# Sheet2.net
KiCad netlist of a schematic drawn in Altium Designer
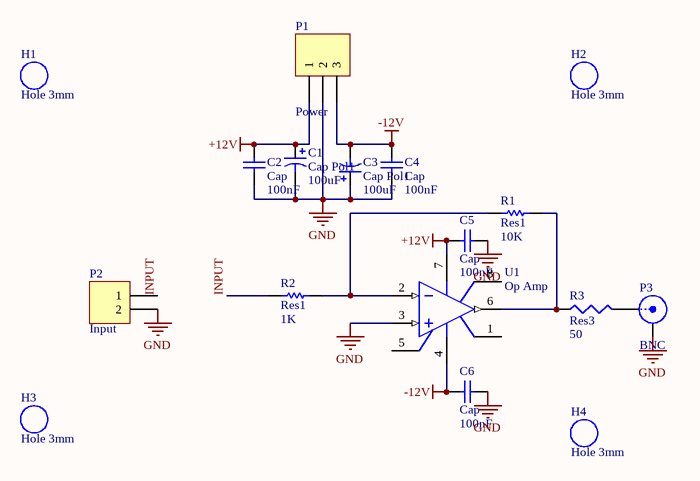
[diagram p0: Sheet2.SchDoc]

(export (version "E")
  (design (tool "Eeschema 10.0.6"))
  (components
    (comp (ref "C1")
      (value "Cap Pol1")
      (footprint "RB7.6-15")
      (description "Polarized Capacitor (Radial)")
      (fields (field (name "ALTIUM_VALUE") "100uF") (field (name "PUBLISHER") "Altium Limited"))
      (libsource (lib "Miscellaneous Devices") (part "Cap Pol1"))
    )
    (comp (ref "C2")
      (value "Cap")
      (footprint "RAD-0.3")
      (description "Capacitor")
      (fields (field (name "ALTIUM_VALUE") "100nF") (field (name "PUBLISHER") "Altium Limited"))
      (libsource (lib "Miscellaneous Devices") (part "Cap"))
    )
    (comp (ref "C3")
      (value "Cap Pol1")
      (footprint "RB7.6-15")
      (description "Polarized Capacitor (Radial)")
      (fields (field (name "ALTIUM_VALUE") "100uF") (field (name "PUBLISHER") "Altium Limited"))
      (libsource (lib "Miscellaneous Devices") (part "Cap Pol1"))
    )
    (comp (ref "C4")
      (value "Cap")
      (footprint "RAD-0.3")
      (description "Capacitor")
      (fields (field (name "ALTIUM_VALUE") "100nF") (field (name "PUBLISHER") "Altium Limited"))
      (libsource (lib "Miscellaneous Devices") (part "Cap"))
    )
    (comp (ref "C5")
      (value "Cap")
      (footprint "RAD-0.3")
      (description "Capacitor")
      (fields (field (name "ALTIUM_VALUE") "100nF") (field (name "PUBLISHER") "Altium Limited"))
      (libsource (lib "Miscellaneous Devices") (part "Cap"))
    )
    (comp (ref "C6")
      (value "Cap")
      (footprint "RAD-0.3")
      (description "Capacitor")
      (fields (field (name "ALTIUM_VALUE") "100nF") (field (name "PUBLISHER") "Altium Limited"))
      (libsource (lib "Miscellaneous Devices") (part "Cap"))
    )
    (comp (ref "H1")
      (value "Hole 3mm")
      (footprint "Hole 3mm")
      (libsource (lib "ECE LIB new") (part "Hole 3mm"))
    )
    (comp (ref "H2")
      (value "Hole 3mm")
      (footprint "Hole 3mm")
      (libsource (lib "ECE LIB new") (part "Hole 3mm"))
    )
    (comp (ref "H3")
      (value "Hole 3mm")
      (footprint "Hole 3mm")
      (libsource (lib "ECE LIB new") (part "Hole 3mm"))
    )
    (comp (ref "H4")
      (value "Hole 3mm")
      (footprint "Hole 3mm")
      (libsource (lib "ECE LIB new") (part "Hole 3mm"))
    )
    (comp (ref "P1")
      (value "Power")
      (footprint "HDR1X3H")
      (description "Header, 3-Pin, Right Angle")
      (fields (field (name "PUBLISHER") "Altium Limited"))
      (libsource (lib "Miscellaneous Connectors") (part "Header 3H"))
    )
    (comp (ref "P2")
      (value "Input")
      (footprint "HDR1X2")
      (description "Header, 2-Pin")
      (fields (field (name "PUBLISHER") "Altium Limited"))
      (libsource (lib "Miscellaneous Connectors") (part "Header 2"))
    )
    (comp (ref "P3")
      (value "BNC")
      (footprint "BNC_RA CON")
      (description "BNC Elbow Connector")
      (fields (field (name "PUBLISHER") "Altium Limited"))
      (libsource (lib "Miscellaneous Connectors") (part "BNC"))
    )
    (comp (ref "R1")
      (value "Res1")
      (footprint "AXIAL-0.3")
      (description "Resistor")
      (fields (field (name "ALTIUM_VALUE") "10K") (field (name "PUBLISHER") "Altium Limited"))
      (libsource (lib "Miscellaneous Devices") (part "Res1"))
    )
    (comp (ref "R2")
      (value "Res1")
      (footprint "AXIAL-0.3")
      (description "Resistor")
      (fields (field (name "ALTIUM_VALUE") "1K") (field (name "PUBLISHER") "Altium Limited"))
      (libsource (lib "Miscellaneous Devices") (part "Res1"))
    )
    (comp (ref "R3")
      (value "Res3")
      (footprint "J1-0603")
      (description "Resistor")
      (fields (field (name "ALTIUM_VALUE") "50") (field (name "PUBLISHER") "Altium Limited"))
      (libsource (lib "Miscellaneous Devices") (part "Res3"))
    )
    (comp (ref "U1")
      (value "Op Amp")
      (footprint "DIP-8")
      (description "FET Operational Amplifier")
      (fields (field (name "PUBLISHER") "Altium Limited"))
      (libsource (lib "Miscellaneous Devices") (part "Op Amp"))
    )
  )
  (nets
    (net (code "1") (name "+12V") (class "Default")
      (node (ref "C1") (pin "1") (pinfunction "1_1") (pintype "passive"))
      (node (ref "C2") (pin "2") (pinfunction "2_2") (pintype "passive"))
      (node (ref "C5") (pin "2") (pinfunction "2_2") (pintype "passive"))
      (node (ref "P1") (pin "1") (pinfunction "1_1") (pintype "passive"))
      (node (ref "U1") (pin "7") (pinfunction "V+_7") (pintype "power_in"))
    )
    (net (code "2") (name "-12V") (class "Default")
      (node (ref "C3") (pin "2") (pinfunction "2_2") (pintype "passive"))
      (node (ref "C4") (pin "2") (pinfunction "2_2") (pintype "passive"))
      (node (ref "C6") (pin "2") (pinfunction "2_2") (pintype "passive"))
      (node (ref "P1") (pin "3") (pinfunction "3_3") (pintype "passive"))
      (node (ref "U1") (pin "4") (pinfunction "V-_4") (pintype "power_in"))
    )
    (net (code "3") (name "/INPUT") (class "Default")
      (node (ref "P2") (pin "1") (pinfunction "1_1") (pintype "passive"))
      (node (ref "R2") (pin "1") (pinfunction "1_1") (pintype "passive"))
    )
    (net (code "4") (name "GND") (class "Default")
      (node (ref "C1") (pin "2") (pinfunction "2_2") (pintype "passive"))
      (node (ref "C2") (pin "1") (pinfunction "1_1") (pintype "passive"))
      (node (ref "C3") (pin "1") (pinfunction "1_1") (pintype "passive"))
      (node (ref "C4") (pin "1") (pinfunction "1_1") (pintype "passive"))
      (node (ref "C5") (pin "1") (pinfunction "1_1") (pintype "passive"))
      (node (ref "C6") (pin "1") (pinfunction "1_1") (pintype "passive"))
      (node (ref "P1") (pin "2") (pinfunction "2_2") (pintype "passive"))
      (node (ref "P2") (pin "2") (pinfunction "2_2") (pintype "passive"))
      (node (ref "P3") (pin "2") (pinfunction "Y_2") (pintype "passive"))
      (node (ref "U1") (pin "3") (pinfunction "IN+_3") (pintype "input"))
    )
    (net (code "5") (name "Net-(P3-X)") (class "Default")
      (node (ref "P3") (pin "1") (pinfunction "X_1") (pintype "passive"))
      (node (ref "R3") (pin "2") (pinfunction "2_2") (pintype "passive"))
    )
    (net (code "6") (name "Net-(U1-IN-)") (class "Default")
      (node (ref "R1") (pin "1") (pinfunction "1_1") (pintype "passive"))
      (node (ref "R2") (pin "2") (pinfunction "2_2") (pintype "passive"))
      (node (ref "U1") (pin "2") (pinfunction "IN-_2") (pintype "input"))
    )
    (net (code "7") (name "Net-(U1-OUT)") (class "Default")
      (node (ref "R1") (pin "2") (pinfunction "2_2") (pintype "passive"))
      (node (ref "R3") (pin "1") (pinfunction "1_1") (pintype "passive"))
      (node (ref "U1") (pin "6") (pinfunction "OUT_6") (pintype "output"))
    )
    (net (code "8") (name "unconnected-(U1-OS_NUL-Pad1)") (class "Default")
      (node (ref "U1") (pin "1") (pinfunction "OS_NUL_1") (pintype "passive"))
    )
    (net (code "9") (name "unconnected-(U1-OS_NUL-Pad5)") (class "Default")
      (node (ref "U1") (pin "5") (pinfunction "OS_NUL_5") (pintype "passive"))
    )
    (net (code "10") (name "unconnected-(U1-TAB-Pad8)") (class "Default")
      (node (ref "U1") (pin "8") (pinfunction "TAB_8") (pintype "passive"))
    )
  )
)
